# ESP32LiPoUSB.net
KiCad netlist of a schematic drawn in EAGLE
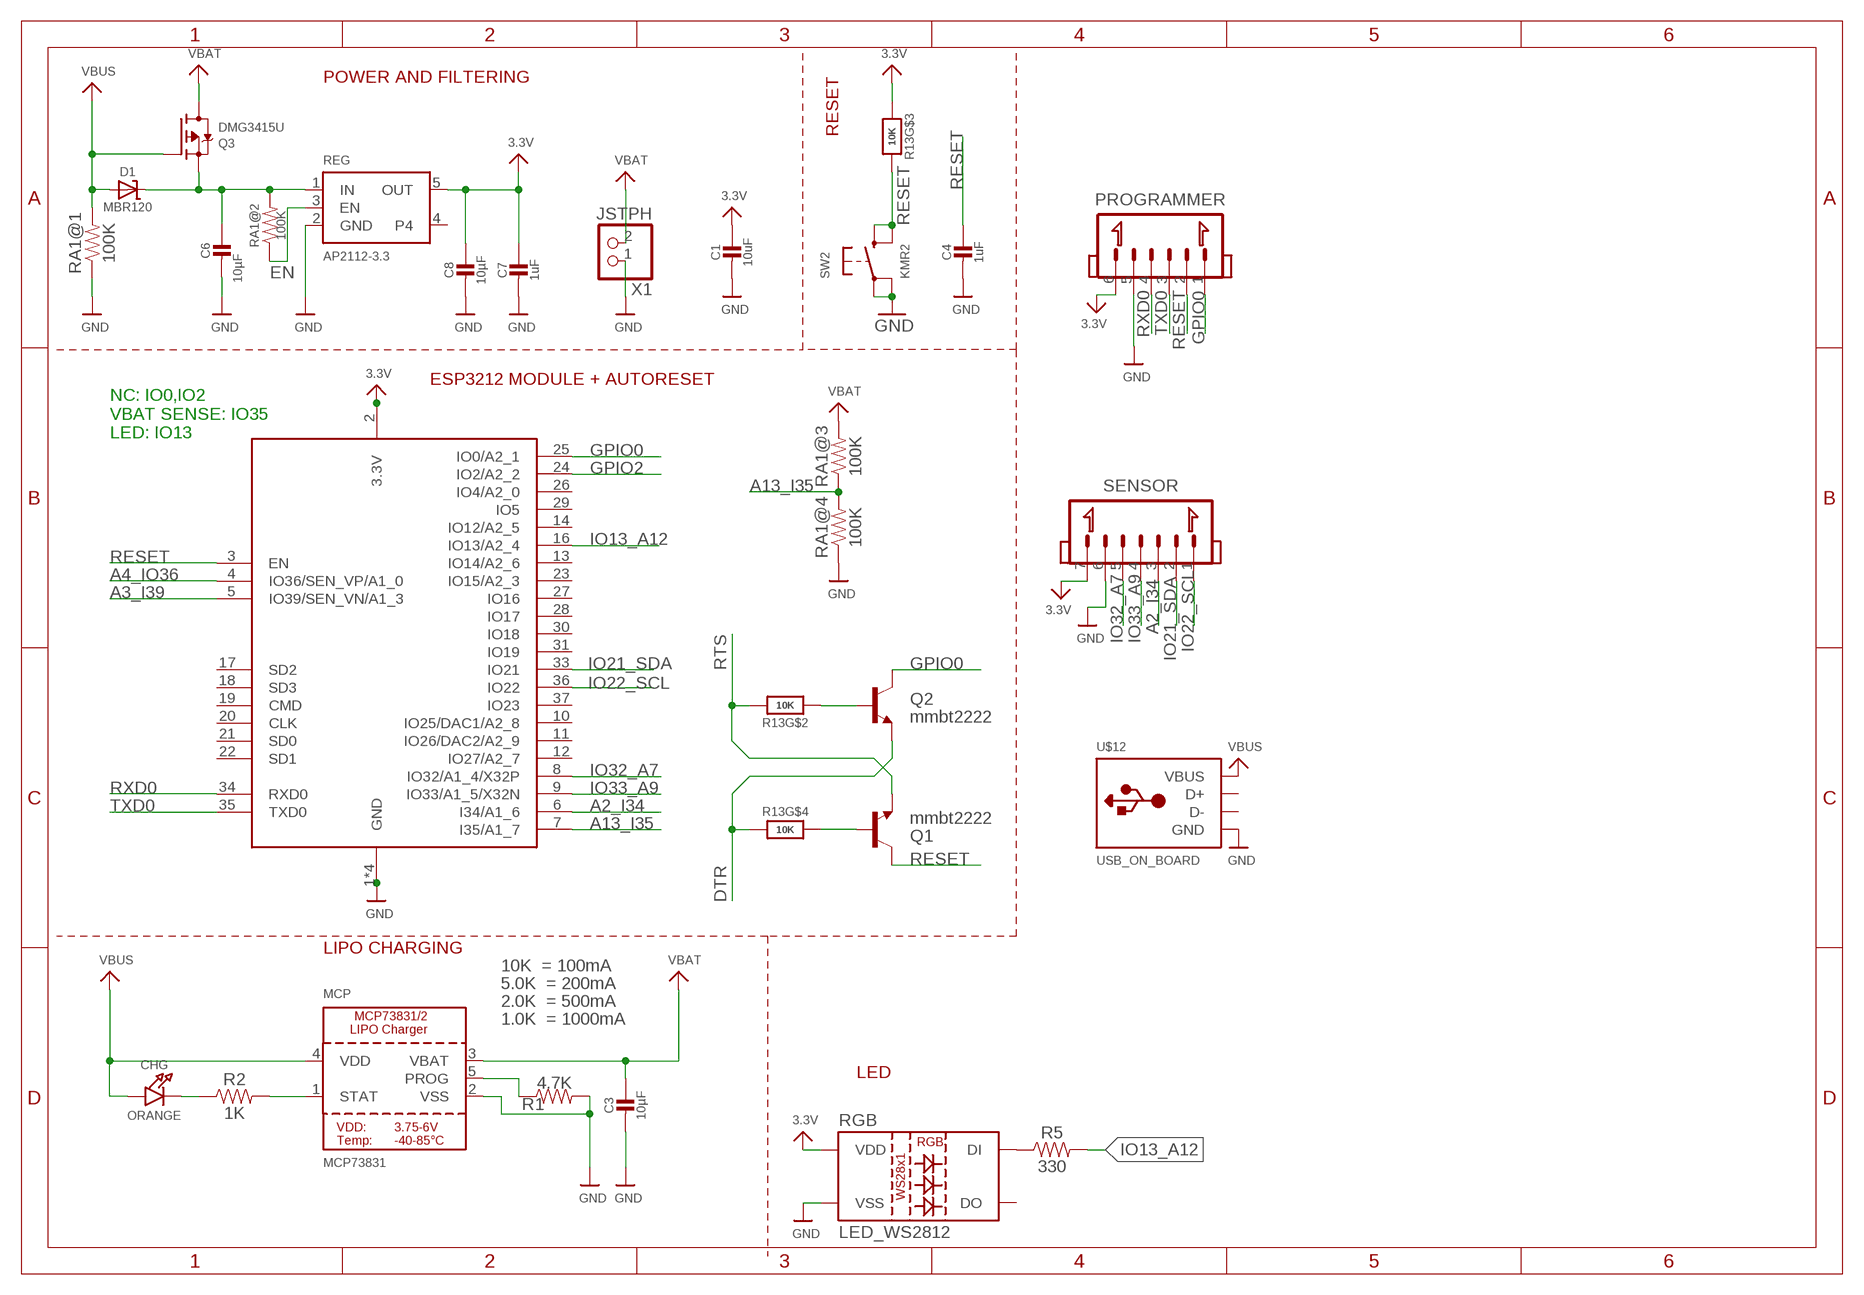
[diagram p0: schematic, sheet 1]

(export (version "E")
  (design (tool "Eeschema 10.0.6"))
  (components
    (comp (ref "C1")
      (value "10uF")
      (footprint "eagle-import:CAP_0805")
      (libsource (lib "eagle-import") (part "CAP_CERAMIC_0805"))
    )
    (comp (ref "C3")
      (value "10µF")
      (footprint "eagle-import:CAP_0805")
      (libsource (lib "eagle-import") (part "CAP_CERAMIC_0805"))
    )
    (comp (ref "C4")
      (value "1uF")
      (footprint "eagle-import:CAP_0603")
      (libsource (lib "eagle-import") (part "CAP_CERAMIC_0603"))
    )
    (comp (ref "C6")
      (value "10µF")
      (footprint "eagle-import:CAP_0603")
      (libsource (lib "eagle-import") (part "CAP_CERAMIC_0603"))
    )
    (comp (ref "C7")
      (value "1uF")
      (footprint "eagle-import:CAP_0603")
      (libsource (lib "eagle-import") (part "CAP_CERAMIC_0603"))
    )
    (comp (ref "C8")
      (value "10µF")
      (footprint "eagle-import:CAP_0805")
      (libsource (lib "eagle-import") (part "CAP_CERAMIC_0805"))
    )
    (comp (ref "CHG")
      (value "ORANGE")
      (footprint "eagle-import:MICROBUILDER_CHIPLED_0603")
      (libsource (lib "eagle-import") (part "LED0603"))
    )
    (comp (ref "D1")
      (value "MBR120")
      (footprint "eagle-import:SOD-123")
      (libsource (lib "eagle-import") (part "DIODE-SCHOTTKYSOD-123"))
    )
    (comp (ref "MCP")
      (value "MCP73831")
      (footprint "eagle-import:SOT23-5")
      (libsource (lib "eagle-import") (part "MCP73831/2"))
    )
    (comp (ref "PROGRAMMER")
      (value "JST_1.25_6P")
      (footprint "eagle-import:JST1.25_6P")
      (libsource (lib "eagle-import") (part "JST_1.25_6P"))
    )
    (comp (ref "Q1")
      (value "mmbt2222")
      (footprint "eagle-import:SOT23-3")
      (libsource (lib "eagle-import") (part "TRANSISTOR_NPNSOT23-3"))
    )
    (comp (ref "Q2")
      (value "mmbt2222")
      (footprint "eagle-import:SOT23-3")
      (libsource (lib "eagle-import") (part "TRANSISTOR_NPNSOT23-3"))
    )
    (comp (ref "Q3")
      (value "DMG3415U")
      (footprint "eagle-import:SOT23-R")
      (libsource (lib "eagle-import") (part "MOSFET-P"))
    )
    (comp (ref "R1")
      (value "4.7K")
      (footprint "eagle-import:0603")
      (libsource (lib "eagle-import") (part "RESISTOR0603"))
    )
    (comp (ref "R2")
      (value "1K")
      (footprint "eagle-import:0603")
      (libsource (lib "eagle-import") (part "RESISTOR0603"))
    )
    (comp (ref "R5")
      (value "330")
      (footprint "eagle-import:0603")
      (libsource (lib "eagle-import") (part "RESISTOR0603"))
    )
    (comp (ref "R13")
      (value "10K")
      (footprint "eagle-import:RESPACK_4X0603")
      (libsource (lib "eagle-import") (part "RESISTOR_4PACK"))
    )
    (comp (ref "RA1")
      (value "100K")
      (footprint "eagle-import:RESCAF80P320X160X60-8N")
      (libsource (lib "eagle-import") (part "RESISTOR_ARRAY_1206_SEPARATE"))
    )
    (comp (ref "REG")
      (value "AP2112-3.3")
      (footprint "eagle-import:SOT23-5")
      (libsource (lib "eagle-import") (part "VREG_SOT23-5"))
    )
    (comp (ref "RGB")
      (value "LED_WS2812")
      (footprint "eagle-import:LED-TRICOLOR-5050-IC")
      (libsource (lib "eagle-import") (part "LED_WS2812"))
    )
    (comp (ref "SENSOR")
      (value "JST_1.25_7P")
      (footprint "eagle-import:JST1.25_7P")
      (libsource (lib "eagle-import") (part "JST_1.25_7P"))
    )
    (comp (ref "SW2")
      (value "KMR2")
      (footprint "eagle-import:BTN_KMR2_4.6X2.8")
      (libsource (lib "eagle-import") (part "SWITCH_TACT_SMT4.6X2.8"))
    )
    (comp (ref "U$12")
      (value "USB_ON_BOARD")
      (footprint "eagle-import:USB_ON_BOARD")
      (libsource (lib "eagle-import") (part "USB_ON_BOARD"))
    )
    (comp (ref "X1")
      (value "JSTPH")
      (footprint "eagle-import:JSTPH2")
      (libsource (lib "eagle-import") (part "CON_JST_PH_2PIN"))
    )
    (comp (ref "X2")
      (value "ESP32_WROOM32_SKINNY")
      (footprint "eagle-import:WROOM32_SKINNY")
      (libsource (lib "eagle-import") (part "ESP32_WROOM32_SKINNY"))
    )
  )
  (nets
    (net (code "1") (name "/A2_I34") (class "Default")
      (node (ref "SENSOR") (pin "3") (pinfunction "3_3") (pintype "passive"))
      (node (ref "X2") (pin "6") (pinfunction "I34/A1_6_6") (pintype "bidirectional"))
    )
    (net (code "2") (name "/A3_I39") (class "Default")
      (node (ref "X2") (pin "5") (pinfunction "IO39/SEN_VN/A1_3_5") (pintype "passive"))
    )
    (net (code "3") (name "/A4_IO36") (class "Default")
      (node (ref "X2") (pin "4") (pinfunction "IO36/SEN_VP/A1_0_4") (pintype "passive"))
    )
    (net (code "4") (name "/A13_I35") (class "Default")
      (node (ref "RA1") (pin "3") (pinfunction "1_3") (pintype "passive"))
      (node (ref "RA1") (pin "8") (pinfunction "2_8") (pintype "passive"))
      (node (ref "X2") (pin "7") (pinfunction "I35/A1_7_7") (pintype "bidirectional"))
    )
    (net (code "5") (name "/DTR") (class "Default")
      (node (ref "Q2") (pin "2") (pinfunction "E_2") (pintype "passive"))
      (node (ref "R13") (pin "4") (pinfunction "1_4") (pintype "passive"))
    )
    (net (code "6") (name "/EN") (class "Default")
      (node (ref "RA1") (pin "2") (pinfunction "1_2") (pintype "passive"))
      (node (ref "REG") (pin "3") (pinfunction "EN_3") (pintype "input"))
    )
    (net (code "7") (name "/GPIO0") (class "Default")
      (node (ref "PROGRAMMER") (pin "1") (pinfunction "1_1") (pintype "passive"))
      (node (ref "Q2") (pin "3") (pinfunction "C_3") (pintype "passive"))
      (node (ref "X2") (pin "25") (pinfunction "IO0/A2_1_25") (pintype "bidirectional"))
    )
    (net (code "8") (name "/GPIO2") (class "Default")
      (node (ref "X2") (pin "24") (pinfunction "IO2/A2_2_24") (pintype "bidirectional"))
    )
    (net (code "9") (name "/IO21_SDA") (class "Default")
      (node (ref "SENSOR") (pin "2") (pinfunction "2_2") (pintype "passive"))
      (node (ref "X2") (pin "33") (pinfunction "IO21_33") (pintype "bidirectional"))
    )
    (net (code "10") (name "/IO22_SCL") (class "Default")
      (node (ref "SENSOR") (pin "1") (pinfunction "1_1") (pintype "passive"))
      (node (ref "X2") (pin "36") (pinfunction "IO22_36") (pintype "bidirectional"))
    )
    (net (code "11") (name "/IO32_A7") (class "Default")
      (node (ref "SENSOR") (pin "5") (pinfunction "5_5") (pintype "passive"))
      (node (ref "X2") (pin "8") (pinfunction "IO32/A1_4/X32P_8") (pintype "bidirectional"))
    )
    (net (code "12") (name "/IO33_A9") (class "Default")
      (node (ref "SENSOR") (pin "4") (pinfunction "4_4") (pintype "passive"))
      (node (ref "X2") (pin "9") (pinfunction "IO33/A1_5/X32N_9") (pintype "bidirectional"))
    )
    (net (code "13") (name "/RESET") (class "Default")
      (node (ref "C4") (pin "1") (pinfunction "1_1") (pintype "passive"))
      (node (ref "PROGRAMMER") (pin "2") (pinfunction "2_2") (pintype "passive"))
      (node (ref "Q1") (pin "3") (pinfunction "C_3") (pintype "passive"))
      (node (ref "R13") (pin "6") (pinfunction "2_6") (pintype "passive"))
      (node (ref "SW2") (pin "B") (pinfunction "S_B") (pintype "passive"))
      (node (ref "SW2") (pin "B'") (pinfunction "S1_B'") (pintype "passive"))
      (node (ref "X2") (pin "3") (pinfunction "EN_3") (pintype "input"))
    )
    (net (code "14") (name "/RTS") (class "Default")
      (node (ref "Q1") (pin "2") (pinfunction "E_2") (pintype "passive"))
      (node (ref "R13") (pin "7") (pinfunction "2_7") (pintype "passive"))
    )
    (net (code "15") (name "/RXD0") (class "Default")
      (node (ref "PROGRAMMER") (pin "4") (pinfunction "4_4") (pintype "passive"))
      (node (ref "X2") (pin "34") (pinfunction "RXD0_34") (pintype "input"))
    )
    (net (code "16") (name "/TXD0") (class "Default")
      (node (ref "PROGRAMMER") (pin "3") (pinfunction "3_3") (pintype "passive"))
      (node (ref "X2") (pin "35") (pinfunction "TXD0_35") (pintype "output"))
    )
    (net (code "17") (name "3.3V") (class "Default")
      (node (ref "C1") (pin "1") (pinfunction "1_1") (pintype "passive"))
      (node (ref "C7") (pin "1") (pinfunction "1_1") (pintype "passive"))
      (node (ref "C8") (pin "1") (pinfunction "1_1") (pintype "passive"))
      (node (ref "PROGRAMMER") (pin "6") (pinfunction "6_6") (pintype "passive"))
      (node (ref "R13") (pin "3") (pinfunction "1_3") (pintype "passive"))
      (node (ref "REG") (pin "5") (pinfunction "OUT_5") (pintype "power_in"))
      (node (ref "RGB") (pin "VDD") (pinfunction "VDD_VDD") (pintype "bidirectional"))
      (node (ref "SENSOR") (pin "7") (pinfunction "7_7") (pintype "passive"))
      (node (ref "X2") (pin "2") (pinfunction "3.3V_2") (pintype "passive"))
    )
    (net (code "18") (name "GND") (class "Default")
      (node (ref "C1") (pin "2") (pinfunction "2_2") (pintype "passive"))
      (node (ref "C3") (pin "2") (pinfunction "2_2") (pintype "passive"))
      (node (ref "C4") (pin "2") (pinfunction "2_2") (pintype "passive"))
      (node (ref "C6") (pin "2") (pinfunction "2_2") (pintype "passive"))
      (node (ref "C7") (pin "2") (pinfunction "2_2") (pintype "passive"))
      (node (ref "C8") (pin "2") (pinfunction "2_2") (pintype "passive"))
      (node (ref "MCP") (pin "2") (pinfunction "VSS_2") (pintype "power_in"))
      (node (ref "PROGRAMMER") (pin "5") (pinfunction "5_5") (pintype "passive"))
      (node (ref "R1") (pin "2") (pinfunction "2_2") (pintype "passive"))
      (node (ref "RA1") (pin "1") (pinfunction "1_1") (pintype "passive"))
      (node (ref "RA1") (pin "4") (pinfunction "1_4") (pintype "passive"))
      (node (ref "REG") (pin "2") (pinfunction "GND_2") (pintype "power_in"))
      (node (ref "RGB") (pin "VSS") (pinfunction "VSS_VSS") (pintype "bidirectional"))
      (node (ref "SENSOR") (pin "6") (pinfunction "6_6") (pintype "passive"))
      (node (ref "SW2") (pin "A") (pinfunction "P_A") (pintype "passive"))
      (node (ref "SW2") (pin "A'") (pinfunction "P1_A'") (pintype "passive"))
      (node (ref "U$12") (pin "GND") (pinfunction "GND_GND") (pintype "power_in"))
      (node (ref "X1") (pin "1") (pinfunction "1_1") (pintype "passive"))
      (node (ref "X2") (pin "1") (pinfunction "GND_1") (pintype "passive"))
      (node (ref "X2") (pin "15") (pinfunction "GND_15") (pintype "passive"))
      (node (ref "X2") (pin "38") (pinfunction "GND_38") (pintype "passive"))
      (node (ref "X2") (pin "P$1") (pinfunction "GND_P$1") (pintype "passive"))
    )
    (net (code "19") (name "IO13_A12") (class "Default")
      (node (ref "R5") (pin "2") (pinfunction "2_2") (pintype "passive"))
      (node (ref "X2") (pin "16") (pinfunction "IO13/A2_4_16") (pintype "bidirectional"))
    )
    (net (code "20") (name "Net-(CHG-PadC)") (class "Default")
      (node (ref "CHG") (pin "C") (pinfunction "C_C") (pintype "passive"))
      (node (ref "R2") (pin "1") (pinfunction "1_1") (pintype "passive"))
    )
    (net (code "21") (name "Net-(MCP-PROG)") (class "Default")
      (node (ref "MCP") (pin "5") (pinfunction "PROG_5") (pintype "input"))
      (node (ref "R1") (pin "1") (pinfunction "1_1") (pintype "passive"))
    )
    (net (code "22") (name "Net-(MCP-STAT)") (class "Default")
      (node (ref "MCP") (pin "1") (pinfunction "STAT_1") (pintype "output"))
      (node (ref "R2") (pin "2") (pinfunction "2_2") (pintype "passive"))
    )
    (net (code "23") (name "Net-(Q1-B)") (class "Default")
      (node (ref "Q1") (pin "1") (pinfunction "B_1") (pintype "passive"))
      (node (ref "R13") (pin "5") (pinfunction "2_5") (pintype "passive"))
    )
    (net (code "24") (name "Net-(Q2-B)") (class "Default")
      (node (ref "Q2") (pin "1") (pinfunction "B_1") (pintype "passive"))
      (node (ref "R13") (pin "2") (pinfunction "1_2") (pintype "passive"))
    )
    (net (code "25") (name "Net-(Q3-S)") (class "Default")
      (node (ref "C6") (pin "1") (pinfunction "1_1") (pintype "passive"))
      (node (ref "D1") (pin "C") (pinfunction "C_C") (pintype "passive"))
      (node (ref "Q3") (pin "2") (pinfunction "S_2") (pintype "passive"))
      (node (ref "RA1") (pin "6") (pinfunction "2_6") (pintype "passive"))
      (node (ref "REG") (pin "1") (pinfunction "IN_1") (pintype "power_in"))
    )
    (net (code "26") (name "Net-(RGB-DI)") (class "Default")
      (node (ref "R5") (pin "1") (pinfunction "1_1") (pintype "passive"))
      (node (ref "RGB") (pin "DIN") (pinfunction "DI_DIN") (pintype "bidirectional"))
    )
    (net (code "27") (name "VBAT") (class "Default")
      (node (ref "C3") (pin "1") (pinfunction "1_1") (pintype "passive"))
      (node (ref "MCP") (pin "3") (pinfunction "VBAT_3") (pintype "power_in"))
      (node (ref "Q3") (pin "3") (pinfunction "D_3") (pintype "passive"))
      (node (ref "RA1") (pin "7") (pinfunction "2_7") (pintype "passive"))
      (node (ref "X1") (pin "2") (pinfunction "2_2") (pintype "passive"))
    )
    (net (code "28") (name "VBUS") (class "Default")
      (node (ref "CHG") (pin "A") (pinfunction "A_A") (pintype "passive"))
      (node (ref "D1") (pin "A") (pinfunction "A_A") (pintype "passive"))
      (node (ref "MCP") (pin "4") (pinfunction "VDD_4") (pintype "power_in"))
      (node (ref "Q3") (pin "1") (pinfunction "G_1") (pintype "passive"))
      (node (ref "RA1") (pin "5") (pinfunction "2_5") (pintype "passive"))
      (node (ref "U$12") (pin "VCC") (pinfunction "VBUS_VCC") (pintype "power_in"))
    )
    (net (code "29") (name "unconnected-(REG-P4-Pad4)") (class "Default")
      (node (ref "REG") (pin "4") (pinfunction "P4_4") (pintype "bidirectional"))
    )
    (net (code "30") (name "unconnected-(RGB-DO-PadDOUT)") (class "Default")
      (node (ref "RGB") (pin "DOUT") (pinfunction "DO_DOUT") (pintype "bidirectional"))
    )
    (net (code "31") (name "unconnected-(U$12-PadD+)") (class "Default")
      (node (ref "U$12") (pin "D+") (pinfunction "D+_D+") (pintype "bidirectional"))
    )
    (net (code "32") (name "unconnected-(U$12-PadD-)") (class "Default")
      (node (ref "U$12") (pin "D-") (pinfunction "D-_D-") (pintype "bidirectional"))
    )
    (net (code "33") (name "unconnected-(X2-CLK-Pad20)") (class "Default")
      (node (ref "X2") (pin "20") (pinfunction "CLK_20") (pintype "bidirectional"))
    )
    (net (code "34") (name "unconnected-(X2-CMD-Pad19)") (class "Default")
      (node (ref "X2") (pin "19") (pinfunction "CMD_19") (pintype "bidirectional"))
    )
    (net (code "35") (name "unconnected-(X2-IO4{slash}A2_0-Pad26)") (class "Default")
      (node (ref "X2") (pin "26") (pinfunction "IO4/A2_0_26") (pintype "bidirectional"))
    )
    (net (code "36") (name "unconnected-(X2-IO5-Pad29)") (class "Default")
      (node (ref "X2") (pin "29") (pinfunction "IO5_29") (pintype "bidirectional"))
    )
    (net (code "37") (name "unconnected-(X2-IO12{slash}A2_5-Pad14)") (class "Default")
      (node (ref "X2") (pin "14") (pinfunction "IO12/A2_5_14") (pintype "bidirectional"))
    )
    (net (code "38") (name "unconnected-(X2-IO14{slash}A2_6-Pad13)") (class "Default")
      (node (ref "X2") (pin "13") (pinfunction "IO14/A2_6_13") (pintype "bidirectional"))
    )
    (net (code "39") (name "unconnected-(X2-IO15{slash}A2_3-Pad23)") (class "Default")
      (node (ref "X2") (pin "23") (pinfunction "IO15/A2_3_23") (pintype "bidirectional"))
    )
    (net (code "40") (name "unconnected-(X2-IO16-Pad27)") (class "Default")
      (node (ref "X2") (pin "27") (pinfunction "IO16_27") (pintype "bidirectional"))
    )
    (net (code "41") (name "unconnected-(X2-IO17-Pad28)") (class "Default")
      (node (ref "X2") (pin "28") (pinfunction "IO17_28") (pintype "bidirectional"))
    )
    (net (code "42") (name "unconnected-(X2-IO18-Pad30)") (class "Default")
      (node (ref "X2") (pin "30") (pinfunction "IO18_30") (pintype "bidirectional"))
    )
    (net (code "43") (name "unconnected-(X2-IO19-Pad31)") (class "Default")
      (node (ref "X2") (pin "31") (pinfunction "IO19_31") (pintype "bidirectional"))
    )
    (net (code "44") (name "unconnected-(X2-IO23-Pad37)") (class "Default")
      (node (ref "X2") (pin "37") (pinfunction "IO23_37") (pintype "bidirectional"))
    )
    (net (code "45") (name "unconnected-(X2-IO25{slash}DAC1{slash}A2_8-Pad10)") (class "Default")
      (node (ref "X2") (pin "10") (pinfunction "IO25/DAC1/A2_8_10") (pintype "bidirectional"))
    )
    (net (code "46") (name "unconnected-(X2-IO26{slash}DAC2{slash}A2_9-Pad11)") (class "Default")
      (node (ref "X2") (pin "11") (pinfunction "IO26/DAC2/A2_9_11") (pintype "bidirectional"))
    )
    (net (code "47") (name "unconnected-(X2-IO27{slash}A2_7-Pad12)") (class "Default")
      (node (ref "X2") (pin "12") (pinfunction "IO27/A2_7_12") (pintype "bidirectional"))
    )
    (net (code "48") (name "unconnected-(X2-SD0-Pad21)") (class "Default")
      (node (ref "X2") (pin "21") (pinfunction "SD0_21") (pintype "bidirectional"))
    )
    (net (code "49") (name "unconnected-(X2-SD1-Pad22)") (class "Default")
      (node (ref "X2") (pin "22") (pinfunction "SD1_22") (pintype "bidirectional"))
    )
    (net (code "50") (name "unconnected-(X2-SD2-Pad17)") (class "Default")
      (node (ref "X2") (pin "17") (pinfunction "SD2_17") (pintype "bidirectional"))
    )
    (net (code "51") (name "unconnected-(X2-SD3-Pad18)") (class "Default")
      (node (ref "X2") (pin "18") (pinfunction "SD3_18") (pintype "bidirectional"))
    )
  )
)
